# Car_PCB.net
KiCad netlist of a schematic drawn in EAGLE
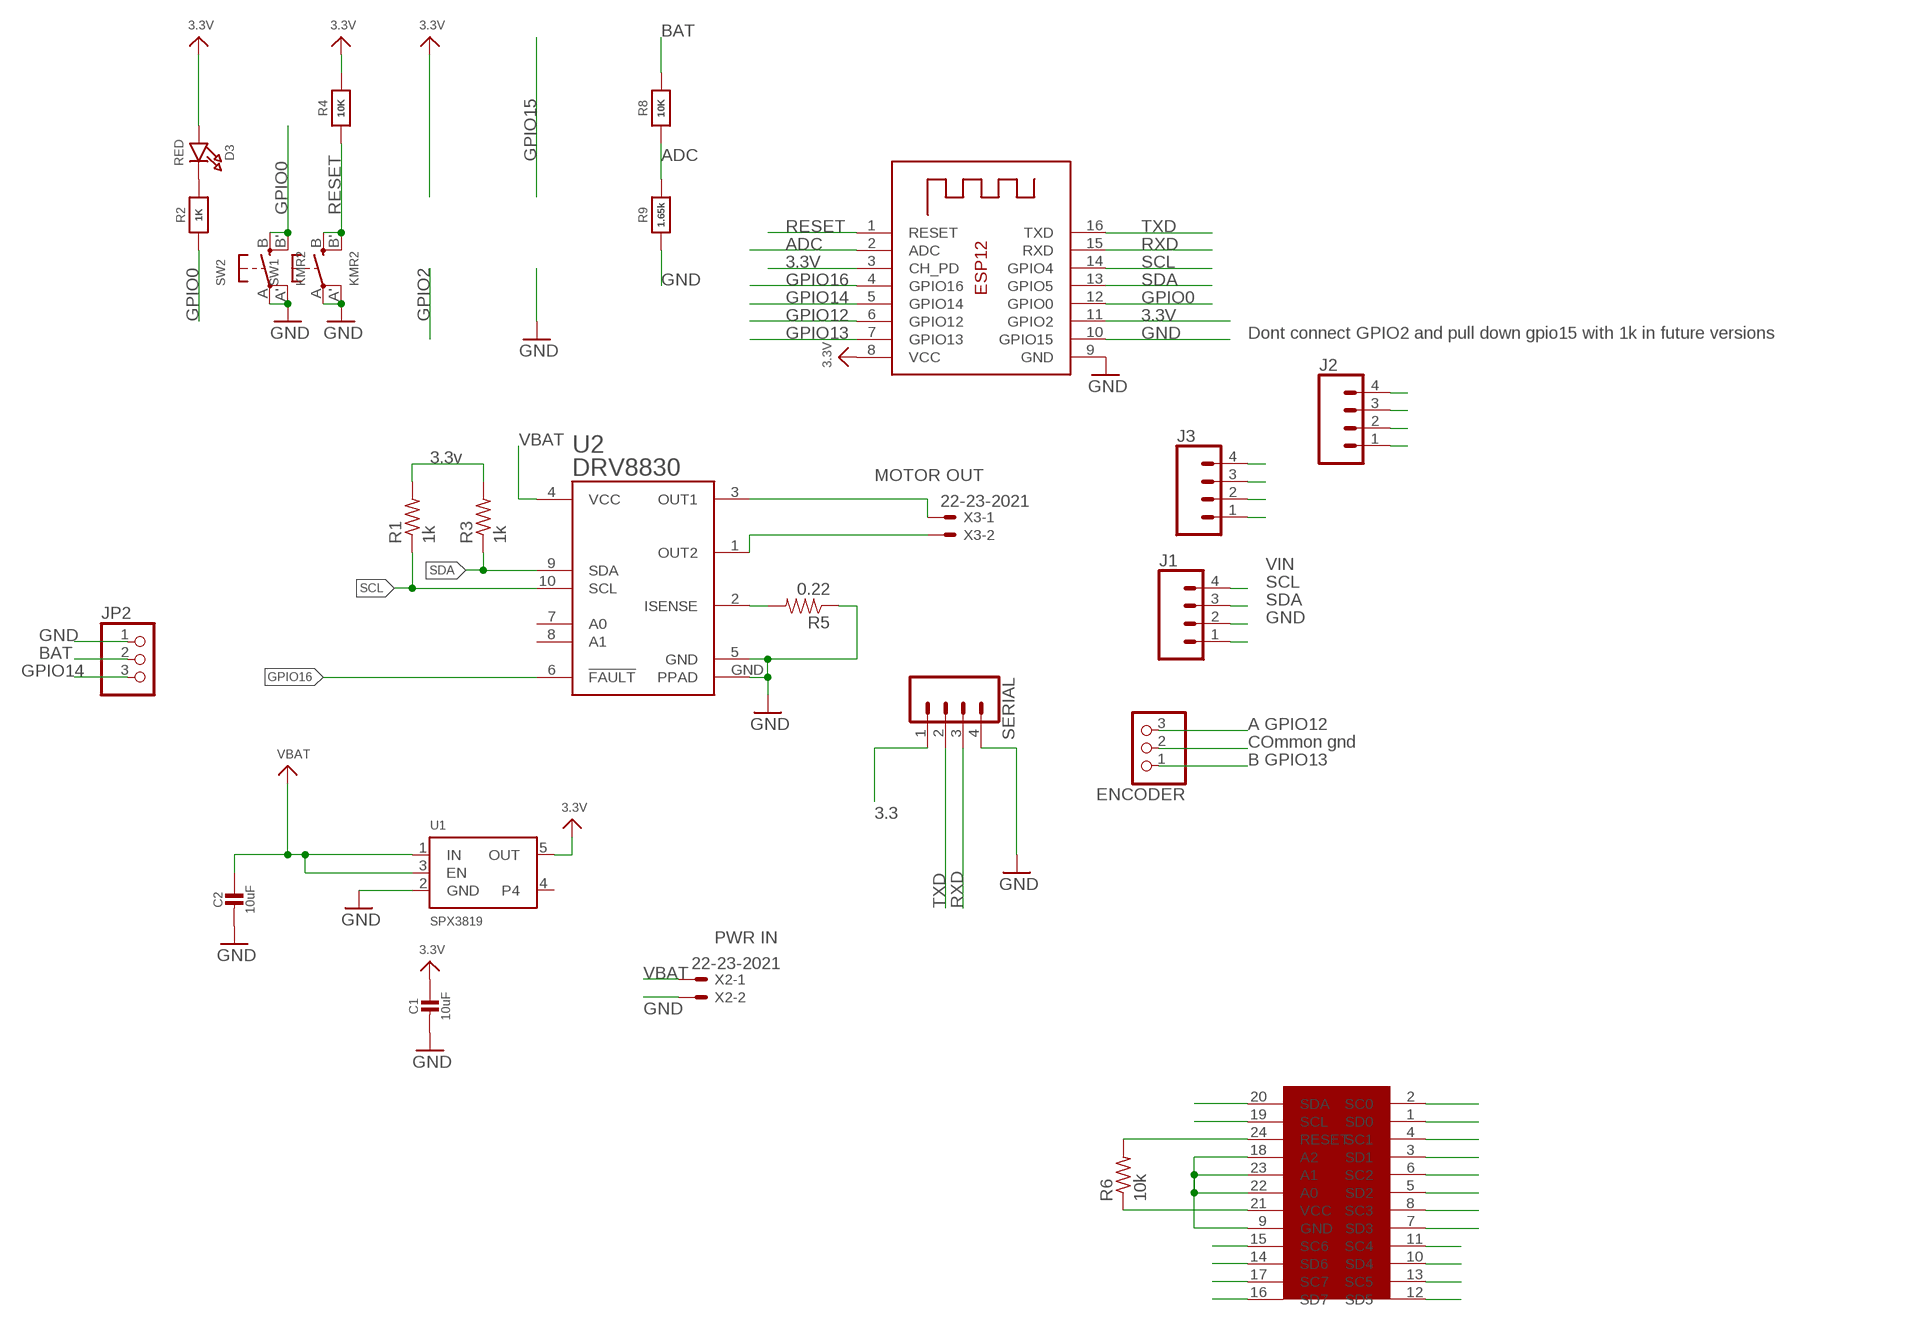
[diagram p0: schematic, sheet 1]

(export (version "E")
  (design (tool "Eeschema 10.0.6"))
  (components
    (comp (ref "C1")
      (value "10uF")
      (footprint "eagle-import:0805-NO")
      (libsource (lib "eagle-import") (part "CAP_CERAMIC0805-NOOUTLINE"))
    )
    (comp (ref "C2")
      (value "10uF")
      (footprint "eagle-import:0805-NO")
      (libsource (lib "eagle-import") (part "CAP_CERAMIC0805-NOOUTLINE"))
    )
    (comp (ref "D3")
      (value "RED")
      (footprint "eagle-import:CHIPLED_0805_NOOUTLINE")
      (libsource (lib "eagle-import") (part "LED0805_NOOUTLINE"))
    )
    (comp (ref "ENCODER")
      (value "PINHD-1X3")
      (footprint "eagle-import:1X03")
      (libsource (lib "eagle-import") (part "PINHD-1X3"))
    )
    (comp (ref "J1")
      (value "CONN_04")
      (footprint "eagle-import:1X04")
      (libsource (lib "eagle-import") (part "CONN_04"))
    )
    (comp (ref "J2")
      (value "CONN_04")
      (footprint "eagle-import:1X04")
      (libsource (lib "eagle-import") (part "CONN_04"))
    )
    (comp (ref "J3")
      (value "CONN_04")
      (footprint "eagle-import:1X04")
      (libsource (lib "eagle-import") (part "CONN_04"))
    )
    (comp (ref "JP2")
      (value "PINHD-1X3")
      (footprint "eagle-import:1X03")
      (libsource (lib "eagle-import") (part "PINHD-1X3"))
    )
    (comp (ref "R1")
      (value "1k")
      (footprint "eagle-import:R0805")
      (libsource (lib "eagle-import") (part "R-US_R0805"))
    )
    (comp (ref "R2")
      (value "1K")
      (footprint "eagle-import:0805-NO")
      (libsource (lib "eagle-import") (part "RESISTOR0805_NOOUTLINE"))
    )
    (comp (ref "R3")
      (value "1k")
      (footprint "eagle-import:R0805")
      (libsource (lib "eagle-import") (part "R-US_R0805"))
    )
    (comp (ref "R4")
      (value "10K")
      (footprint "eagle-import:0805-NO")
      (libsource (lib "eagle-import") (part "RESISTOR0805_NOOUTLINE"))
    )
    (comp (ref "R5")
      (value "0.22")
      (footprint "eagle-import:0805")
      (libsource (lib "eagle-import") (part "0.22OHM1/4W1%(0805)"))
    )
    (comp (ref "R6")
      (value "10k")
      (footprint "eagle-import:M0805")
      (libsource (lib "eagle-import") (part "R-US_M0805"))
    )
    (comp (ref "R8")
      (value "10K")
      (footprint "eagle-import:0805-NO")
      (libsource (lib "eagle-import") (part "RESISTOR0805_NOOUTLINE"))
    )
    (comp (ref "R9")
      (value "1.65k")
      (footprint "eagle-import:0805-NO")
      (libsource (lib "eagle-import") (part "RESISTOR0805_NOOUTLINE"))
    )
    (comp (ref "SERIAL")
      (value "CONN_04")
      (footprint "eagle-import:1X04")
      (libsource (lib "eagle-import") (part "CONN_04"))
    )
    (comp (ref "SW1")
      (value "KMR2")
      (footprint "eagle-import:BTN_KMR2_4.6X2.8")
      (libsource (lib "eagle-import") (part "SWITCH_TACT_SMT4.6X2.8"))
    )
    (comp (ref "SW2")
      (value "KMR2")
      (footprint "eagle-import:BTN_KMR2_4.6X2.8")
      (libsource (lib "eagle-import") (part "SWITCH_TACT_SMT4.6X2.8"))
    )
    (comp (ref "U$1")
      (value "TCA9548A")
      (footprint "eagle-import:QFN24-4X4")
      (libsource (lib "eagle-import") (part "TCA9548A"))
    )
    (comp (ref "U1")
      (value "SPX3819")
      (footprint "eagle-import:SOT23-5")
      (libsource (lib "eagle-import") (part "VREG_SOT23-5"))
    )
    (comp (ref "U2")
      (value "DRV8830")
      (footprint "eagle-import:MSOP-10-GNDPAD")
      (libsource (lib "eagle-import") (part "DRV8830"))
    )
    (comp (ref "X1")
      (value "ESP-12")
      (footprint "eagle-import:ESP-12")
      (libsource (lib "eagle-import") (part "ESP-12"))
    )
    (comp (ref "X2")
      (value "22-23-2021")
      (footprint "eagle-import:22-23-2021")
      (fields (field (name "MF") "MOLEX"))
      (libsource (lib "eagle-import") (part "22-23-2021"))
    )
    (comp (ref "X3")
      (value "22-23-2021")
      (footprint "eagle-import:22-23-2021")
      (fields (field (name "MF") "MOLEX"))
      (libsource (lib "eagle-import") (part "22-23-2021"))
    )
  )
  (nets
    (net (code "1") (name "/ADC") (class "Default")
      (node (ref "R8") (pin "1") (pinfunction "1_1") (pintype "passive"))
      (node (ref "R9") (pin "2") (pinfunction "2_2") (pintype "passive"))
      (node (ref "X1") (pin "2") (pinfunction "ADC_2") (pintype "passive"))
    )
    (net (code "2") (name "/GPIO0") (class "Default")
      (node (ref "R2") (pin "1") (pinfunction "1_1") (pintype "passive"))
      (node (ref "SW2") (pin "B") (pinfunction "S_B") (pintype "passive"))
      (node (ref "SW2") (pin "B'") (pinfunction "S1_B'") (pintype "passive"))
      (node (ref "X1") (pin "12") (pinfunction "GPIO0_12") (pintype "bidirectional"))
    )
    (net (code "4") (name "/GPIO12") (class "Default")
      (node (ref "ENCODER") (pin "3") (pinfunction "3_3") (pintype "passive"))
      (node (ref "X1") (pin "6") (pinfunction "GPIO12_6") (pintype "bidirectional"))
    )
    (net (code "5") (name "/GPIO13") (class "Default")
      (node (ref "ENCODER") (pin "1") (pinfunction "1_1") (pintype "passive"))
      (node (ref "X1") (pin "7") (pinfunction "GPIO13_7") (pintype "bidirectional"))
    )
    (net (code "6") (name "/GPIO14") (class "Default")
      (node (ref "JP2") (pin "3") (pinfunction "3_3") (pintype "passive"))
      (node (ref "X1") (pin "5") (pinfunction "GPIO14_5") (pintype "bidirectional"))
    )
    (net (code "8") (name "/RESET") (class "Default")
      (node (ref "R4") (pin "1") (pinfunction "1_1") (pintype "passive"))
      (node (ref "SW1") (pin "B") (pinfunction "S_B") (pintype "passive"))
      (node (ref "SW1") (pin "B'") (pinfunction "S1_B'") (pintype "passive"))
      (node (ref "X1") (pin "1") (pinfunction "RESET_1") (pintype "input"))
    )
    (net (code "9") (name "/RXD") (class "Default")
      (node (ref "SERIAL") (pin "3") (pinfunction "3_3") (pintype "passive"))
      (node (ref "X1") (pin "15") (pinfunction "RXD_15") (pintype "input"))
    )
    (net (code "10") (name "/SC3") (class "Default")
      (node (ref "J3") (pin "2") (pinfunction "2_2") (pintype "passive"))
      (node (ref "U$1") (pin "8") (pinfunction "SC3_8") (pintype "bidirectional"))
    )
    (net (code "11") (name "/SC5") (class "Default")
      (node (ref "J2") (pin "2") (pinfunction "2_2") (pintype "passive"))
      (node (ref "U$1") (pin "13") (pinfunction "SC5_13") (pintype "bidirectional"))
    )
    (net (code "12") (name "/SC6") (class "Default")
      (node (ref "J1") (pin "2") (pinfunction "2_2") (pintype "passive"))
      (node (ref "U$1") (pin "15") (pinfunction "SC6_15") (pintype "bidirectional"))
    )
    (net (code "13") (name "/SD3") (class "Default")
      (node (ref "J3") (pin "3") (pinfunction "3_3") (pintype "passive"))
      (node (ref "U$1") (pin "7") (pinfunction "SD3_7") (pintype "bidirectional"))
    )
    (net (code "14") (name "/SD5") (class "Default")
      (node (ref "J2") (pin "3") (pinfunction "3_3") (pintype "passive"))
      (node (ref "U$1") (pin "12") (pinfunction "SD5_12") (pintype "bidirectional"))
    )
    (net (code "15") (name "/SD6") (class "Default")
      (node (ref "J1") (pin "3") (pinfunction "3_3") (pintype "passive"))
      (node (ref "U$1") (pin "14") (pinfunction "SD6_14") (pintype "bidirectional"))
    )
    (net (code "16") (name "/TXD") (class "Default")
      (node (ref "SERIAL") (pin "2") (pinfunction "2_2") (pintype "passive"))
      (node (ref "X1") (pin "16") (pinfunction "TXD_16") (pintype "output"))
    )
    (net (code "17") (name "3.3V") (class "Default")
      (node (ref "C1") (pin "1") (pinfunction "1_1") (pintype "passive"))
      (node (ref "D3") (pin "A") (pinfunction "A_A") (pintype "passive"))
      (node (ref "J1") (pin "4") (pinfunction "4_4") (pintype "passive"))
      (node (ref "J2") (pin "4") (pinfunction "4_4") (pintype "passive"))
      (node (ref "J3") (pin "4") (pinfunction "4_4") (pintype "passive"))
      (node (ref "R1") (pin "2") (pinfunction "2_2") (pintype "passive"))
      (node (ref "R3") (pin "2") (pinfunction "2_2") (pintype "passive"))
      (node (ref "R4") (pin "2") (pinfunction "2_2") (pintype "passive"))
      (node (ref "R6") (pin "1") (pinfunction "1_1") (pintype "passive"))
      (node (ref "SERIAL") (pin "1") (pinfunction "1_1") (pintype "passive"))
      (node (ref "U$1") (pin "21") (pinfunction "VCC_21") (pintype "bidirectional"))
      (node (ref "U1") (pin "5") (pinfunction "OUT_5") (pintype "power_in"))
      (node (ref "X1") (pin "11") (pinfunction "GPIO2_11") (pintype "bidirectional"))
      (node (ref "X1") (pin "3") (pinfunction "CH_PD_3") (pintype "input"))
      (node (ref "X1") (pin "8") (pinfunction "VCC_8") (pintype "power_in"))
    )
    (net (code "18") (name "GND") (class "Default")
      (node (ref "C1") (pin "2") (pinfunction "2_2") (pintype "passive"))
      (node (ref "C2") (pin "2") (pinfunction "2_2") (pintype "passive"))
      (node (ref "ENCODER") (pin "2") (pinfunction "2_2") (pintype "passive"))
      (node (ref "J1") (pin "1") (pinfunction "1_1") (pintype "passive"))
      (node (ref "J2") (pin "1") (pinfunction "1_1") (pintype "passive"))
      (node (ref "J3") (pin "1") (pinfunction "1_1") (pintype "passive"))
      (node (ref "JP2") (pin "1") (pinfunction "1_1") (pintype "passive"))
      (node (ref "R5") (pin "1") (pinfunction "1_1") (pintype "passive"))
      (node (ref "R9") (pin "1") (pinfunction "1_1") (pintype "passive"))
      (node (ref "SERIAL") (pin "4") (pinfunction "4_4") (pintype "passive"))
      (node (ref "SW1") (pin "A") (pinfunction "P_A") (pintype "passive"))
      (node (ref "SW1") (pin "A'") (pinfunction "P1_A'") (pintype "passive"))
      (node (ref "SW2") (pin "A") (pinfunction "P_A") (pintype "passive"))
      (node (ref "SW2") (pin "A'") (pinfunction "P1_A'") (pintype "passive"))
      (node (ref "U$1") (pin "18") (pinfunction "A2_18") (pintype "bidirectional"))
      (node (ref "U$1") (pin "22") (pinfunction "A0_22") (pintype "bidirectional"))
      (node (ref "U$1") (pin "23") (pinfunction "A1_23") (pintype "bidirectional"))
      (node (ref "U$1") (pin "9") (pinfunction "GND_9") (pintype "bidirectional"))
      (node (ref "U1") (pin "2") (pinfunction "GND_2") (pintype "power_in"))
      (node (ref "U2") (pin "5") (pinfunction "GND_5") (pintype "bidirectional"))
      (node (ref "U2") (pin "GND") (pinfunction "PPAD_GND") (pintype "bidirectional"))
      (node (ref "X1") (pin "10") (pinfunction "GPIO15_10") (pintype "bidirectional"))
      (node (ref "X1") (pin "9") (pinfunction "GND_9") (pintype "power_in"))
      (node (ref "X2") (pin "2") (pinfunction "S_2") (pintype "passive"))
    )
    (net (code "19") (name "GPIO16") (class "Default")
      (node (ref "U2") (pin "6") (pinfunction "~{FAULT}_6") (pintype "bidirectional"))
      (node (ref "X1") (pin "4") (pinfunction "GPIO16_4") (pintype "bidirectional"))
    )
    (net (code "20") (name "Net-(D3-PadC)") (class "Default")
      (node (ref "D3") (pin "C") (pinfunction "C_C") (pintype "passive"))
      (node (ref "R2") (pin "2") (pinfunction "2_2") (pintype "passive"))
    )
    (net (code "21") (name "Net-(U$1-RESET)") (class "Default")
      (node (ref "R6") (pin "2") (pinfunction "2_2") (pintype "passive"))
      (node (ref "U$1") (pin "24") (pinfunction "RESET_24") (pintype "bidirectional"))
    )
    (net (code "22") (name "Net-(U2-ISENSE)") (class "Default")
      (node (ref "R5") (pin "2") (pinfunction "2_2") (pintype "passive"))
      (node (ref "U2") (pin "2") (pinfunction "ISENSE_2") (pintype "bidirectional"))
    )
    (net (code "23") (name "Net-(U2-OUT1)") (class "Default")
      (node (ref "U2") (pin "3") (pinfunction "OUT1_3") (pintype "bidirectional"))
      (node (ref "X3") (pin "1") (pinfunction "S_1") (pintype "passive"))
    )
    (net (code "24") (name "Net-(U2-OUT2)") (class "Default")
      (node (ref "U2") (pin "1") (pinfunction "OUT2_1") (pintype "bidirectional"))
      (node (ref "X3") (pin "2") (pinfunction "S_2") (pintype "passive"))
    )
    (net (code "25") (name "SCL") (class "Default")
      (node (ref "R1") (pin "1") (pinfunction "1_1") (pintype "passive"))
      (node (ref "U$1") (pin "19") (pinfunction "SCL_19") (pintype "bidirectional"))
      (node (ref "U2") (pin "10") (pinfunction "SCL_10") (pintype "bidirectional"))
      (node (ref "X1") (pin "14") (pinfunction "GPIO4_14") (pintype "bidirectional"))
    )
    (net (code "26") (name "SDA") (class "Default")
      (node (ref "R3") (pin "1") (pinfunction "1_1") (pintype "passive"))
      (node (ref "U$1") (pin "20") (pinfunction "SDA_20") (pintype "bidirectional"))
      (node (ref "U2") (pin "9") (pinfunction "SDA_9") (pintype "bidirectional"))
      (node (ref "X1") (pin "13") (pinfunction "GPIO5_13") (pintype "bidirectional"))
    )
    (net (code "27") (name "VBAT") (class "Default")
      (node (ref "C2") (pin "1") (pinfunction "1_1") (pintype "passive"))
      (node (ref "JP2") (pin "2") (pinfunction "2_2") (pintype "passive"))
      (node (ref "R8") (pin "2") (pinfunction "2_2") (pintype "passive"))
      (node (ref "U1") (pin "1") (pinfunction "IN_1") (pintype "power_in"))
      (node (ref "U1") (pin "3") (pinfunction "EN_3") (pintype "input"))
      (node (ref "U2") (pin "4") (pinfunction "VCC_4") (pintype "bidirectional"))
      (node (ref "X2") (pin "1") (pinfunction "S_1") (pintype "passive"))
    )
    (net (code "28") (name "unconnected-(U$1-SC0-Pad2)") (class "Default")
      (node (ref "U$1") (pin "2") (pinfunction "SC0_2") (pintype "bidirectional"))
    )
    (net (code "29") (name "unconnected-(U$1-SC1-Pad4)") (class "Default")
      (node (ref "U$1") (pin "4") (pinfunction "SC1_4") (pintype "bidirectional"))
    )
    (net (code "30") (name "unconnected-(U$1-SC2-Pad6)") (class "Default")
      (node (ref "U$1") (pin "6") (pinfunction "SC2_6") (pintype "bidirectional"))
    )
    (net (code "31") (name "unconnected-(U$1-SC4-Pad11)") (class "Default")
      (node (ref "U$1") (pin "11") (pinfunction "SC4_11") (pintype "bidirectional"))
    )
    (net (code "32") (name "unconnected-(U$1-SC7-Pad17)") (class "Default")
      (node (ref "U$1") (pin "17") (pinfunction "SC7_17") (pintype "bidirectional"))
    )
    (net (code "33") (name "unconnected-(U$1-SD0-Pad1)") (class "Default")
      (node (ref "U$1") (pin "1") (pinfunction "SD0_1") (pintype "bidirectional"))
    )
    (net (code "34") (name "unconnected-(U$1-SD1-Pad3)") (class "Default")
      (node (ref "U$1") (pin "3") (pinfunction "SD1_3") (pintype "bidirectional"))
    )
    (net (code "35") (name "unconnected-(U$1-SD2-Pad5)") (class "Default")
      (node (ref "U$1") (pin "5") (pinfunction "SD2_5") (pintype "bidirectional"))
    )
    (net (code "36") (name "unconnected-(U$1-SD4-Pad10)") (class "Default")
      (node (ref "U$1") (pin "10") (pinfunction "SD4_10") (pintype "bidirectional"))
    )
    (net (code "37") (name "unconnected-(U$1-SD7-Pad16)") (class "Default")
      (node (ref "U$1") (pin "16") (pinfunction "SD7_16") (pintype "bidirectional"))
    )
    (net (code "38") (name "unconnected-(U1-P4-Pad4)") (class "Default")
      (node (ref "U1") (pin "4") (pinfunction "P4_4") (pintype "bidirectional"))
    )
    (net (code "39") (name "unconnected-(U2-A0-Pad7)") (class "Default")
      (node (ref "U2") (pin "7") (pinfunction "A0_7") (pintype "bidirectional"))
    )
    (net (code "40") (name "unconnected-(U2-A1-Pad8)") (class "Default")
      (node (ref "U2") (pin "8") (pinfunction "A1_8") (pintype "bidirectional"))
    )
  )
)
